# PCB3.net
KiCad netlist of a schematic drawn in EAGLE
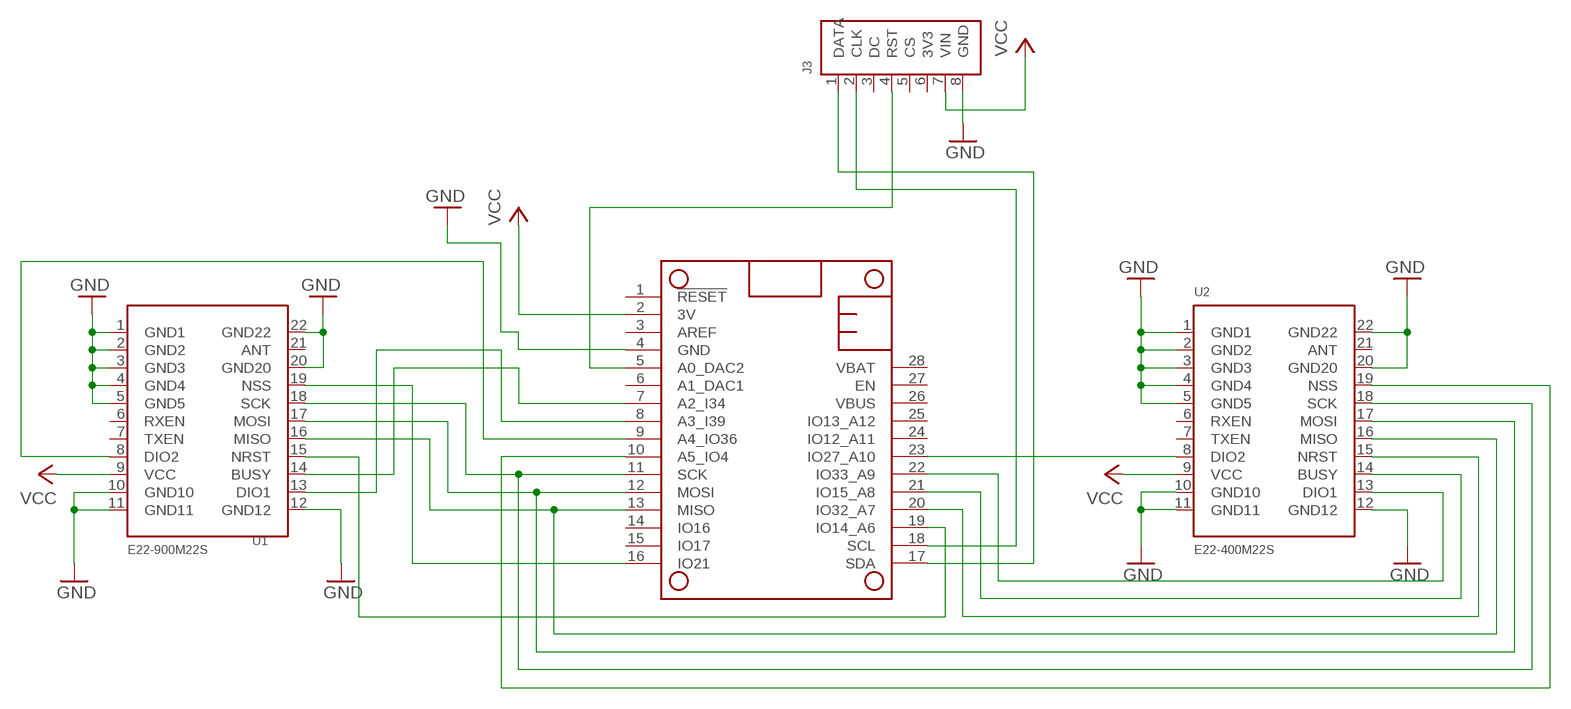
[diagram p0: schematic, sheet 1]

(export (version "E")
  (design (tool "Eeschema 10.0.6"))
  (components
    (comp (ref "J3")
      (value "1.3\"_128X64")
      (footprint "eagle-import:1.3__128X64_OLED")
      (libsource (lib "eagle-import") (part "1.3{dblquote}_128X64"))
    )
    (comp (ref "MS1")
      (value "FEATHERWING")
      (footprint "eagle-import:FEATHERWING")
      (libsource (lib "eagle-import") (part "FEATHERWING"))
    )
    (comp (ref "U1")
      (value "E22-900M22S")
      (footprint "eagle-import:E22")
      (libsource (lib "eagle-import") (part "E22-900M22S"))
    )
    (comp (ref "U2")
      (value "E22-400M22S")
      (footprint "eagle-import:E22")
      (libsource (lib "eagle-import") (part "E22-400M22S"))
    )
  )
  (nets
    (net (code "1") (name "/3V3") (class "Default")
      (node (ref "J3") (pin "6") (pinfunction "3V3_6") (pintype "power_in"))
    )
    (net (code "2") (name "/VBAT") (class "Default")
      (node (ref "MS1") (pin "28") (pinfunction "VBAT_28") (pintype "power_in"))
    )
    (net (code "3") (name "/VBUS") (class "Default")
      (node (ref "MS1") (pin "26") (pinfunction "VBUS_26") (pintype "power_in"))
    )
    (net (code "4") (name "GND") (class "Default")
      (node (ref "J3") (pin "8") (pinfunction "GND_8") (pintype "power_in"))
      (node (ref "MS1") (pin "4") (pinfunction "GND_4") (pintype "power_in"))
      (node (ref "U1") (pin "1") (pinfunction "GND1_1") (pintype "power_in"))
      (node (ref "U1") (pin "10") (pinfunction "GND10_10") (pintype "power_in"))
      (node (ref "U1") (pin "11") (pinfunction "GND11_11") (pintype "power_in"))
      (node (ref "U1") (pin "12") (pinfunction "GND12_12") (pintype "power_in"))
      (node (ref "U1") (pin "2") (pinfunction "GND2_2") (pintype "power_in"))
      (node (ref "U1") (pin "20") (pinfunction "GND20_20") (pintype "power_in"))
      (node (ref "U1") (pin "22") (pinfunction "GND22_22") (pintype "power_in"))
      (node (ref "U1") (pin "3") (pinfunction "GND3_3") (pintype "power_in"))
      (node (ref "U1") (pin "4") (pinfunction "GND4_4") (pintype "power_in"))
      (node (ref "U1") (pin "5") (pinfunction "GND5_5") (pintype "power_in"))
      (node (ref "U2") (pin "1") (pinfunction "GND1_1") (pintype "power_in"))
      (node (ref "U2") (pin "10") (pinfunction "GND10_10") (pintype "power_in"))
      (node (ref "U2") (pin "11") (pinfunction "GND11_11") (pintype "power_in"))
      (node (ref "U2") (pin "12") (pinfunction "GND12_12") (pintype "power_in"))
      (node (ref "U2") (pin "2") (pinfunction "GND2_2") (pintype "power_in"))
      (node (ref "U2") (pin "20") (pinfunction "GND20_20") (pintype "power_in"))
      (node (ref "U2") (pin "22") (pinfunction "GND22_22") (pintype "power_in"))
      (node (ref "U2") (pin "3") (pinfunction "GND3_3") (pintype "power_in"))
      (node (ref "U2") (pin "4") (pinfunction "GND4_4") (pintype "power_in"))
      (node (ref "U2") (pin "5") (pinfunction "GND5_5") (pintype "power_in"))
    )
    (net (code "5") (name "Net-(J3-CLK)") (class "Default")
      (node (ref "J3") (pin "2") (pinfunction "CLK_2") (pintype "bidirectional"))
      (node (ref "MS1") (pin "18") (pinfunction "SCL_18") (pintype "bidirectional"))
    )
    (net (code "6") (name "Net-(J3-DATA)") (class "Default")
      (node (ref "J3") (pin "1") (pinfunction "DATA_1") (pintype "bidirectional"))
      (node (ref "MS1") (pin "17") (pinfunction "SDA_17") (pintype "bidirectional"))
    )
    (net (code "7") (name "Net-(J3-RST)") (class "Default")
      (node (ref "J3") (pin "4") (pinfunction "RST_4") (pintype "bidirectional"))
      (node (ref "MS1") (pin "5") (pinfunction "A0_DAC2_5") (pintype "bidirectional"))
    )
    (net (code "8") (name "Net-(MS1-A2_I34)") (class "Default")
      (node (ref "MS1") (pin "7") (pinfunction "A2_I34_7") (pintype "bidirectional"))
      (node (ref "U1") (pin "14") (pinfunction "BUSY_14") (pintype "output"))
    )
    (net (code "9") (name "Net-(MS1-A3_I39)") (class "Default")
      (node (ref "MS1") (pin "8") (pinfunction "A3_I39_8") (pintype "bidirectional"))
      (node (ref "U1") (pin "13") (pinfunction "DIO1_13") (pintype "bidirectional"))
    )
    (net (code "10") (name "Net-(MS1-A4_IO36)") (class "Default")
      (node (ref "MS1") (pin "9") (pinfunction "A4_IO36_9") (pintype "bidirectional"))
      (node (ref "U1") (pin "8") (pinfunction "DIO2_8") (pintype "bidirectional"))
    )
    (net (code "11") (name "Net-(MS1-A5_IO4)") (class "Default")
      (node (ref "MS1") (pin "10") (pinfunction "A5_IO4_10") (pintype "bidirectional"))
      (node (ref "U2") (pin "19") (pinfunction "NSS_19") (pintype "input"))
    )
    (net (code "12") (name "Net-(MS1-IO14_A6)") (class "Default")
      (node (ref "MS1") (pin "19") (pinfunction "IO14_A6_19") (pintype "bidirectional"))
      (node (ref "U1") (pin "15") (pinfunction "NRST_15") (pintype "input"))
    )
    (net (code "13") (name "Net-(MS1-IO15_A8)") (class "Default")
      (node (ref "MS1") (pin "21") (pinfunction "IO15_A8_21") (pintype "bidirectional"))
      (node (ref "U2") (pin "14") (pinfunction "BUSY_14") (pintype "output"))
    )
    (net (code "14") (name "Net-(MS1-IO21)") (class "Default")
      (node (ref "MS1") (pin "16") (pinfunction "IO21_16") (pintype "bidirectional"))
      (node (ref "U1") (pin "19") (pinfunction "NSS_19") (pintype "input"))
    )
    (net (code "15") (name "Net-(MS1-IO27_A10)") (class "Default")
      (node (ref "MS1") (pin "23") (pinfunction "IO27_A10_23") (pintype "bidirectional"))
      (node (ref "U2") (pin "8") (pinfunction "DIO2_8") (pintype "bidirectional"))
    )
    (net (code "16") (name "Net-(MS1-IO32_A7)") (class "Default")
      (node (ref "MS1") (pin "20") (pinfunction "IO32_A7_20") (pintype "bidirectional"))
      (node (ref "U2") (pin "15") (pinfunction "NRST_15") (pintype "input"))
    )
    (net (code "17") (name "Net-(MS1-IO33_A9)") (class "Default")
      (node (ref "MS1") (pin "22") (pinfunction "IO33_A9_22") (pintype "bidirectional"))
      (node (ref "U2") (pin "13") (pinfunction "DIO1_13") (pintype "bidirectional"))
    )
    (net (code "18") (name "Net-(MS1-MISO)") (class "Default")
      (node (ref "MS1") (pin "13") (pinfunction "MISO_13") (pintype "bidirectional"))
      (node (ref "U1") (pin "16") (pinfunction "MISO_16") (pintype "output"))
      (node (ref "U2") (pin "16") (pinfunction "MISO_16") (pintype "output"))
    )
    (net (code "19") (name "Net-(MS1-MOSI)") (class "Default")
      (node (ref "MS1") (pin "12") (pinfunction "MOSI_12") (pintype "bidirectional"))
      (node (ref "U1") (pin "17") (pinfunction "MOSI_17") (pintype "input"))
      (node (ref "U2") (pin "17") (pinfunction "MOSI_17") (pintype "input"))
    )
    (net (code "20") (name "Net-(MS1-SCK)") (class "Default")
      (node (ref "MS1") (pin "11") (pinfunction "SCK_11") (pintype "bidirectional"))
      (node (ref "U1") (pin "18") (pinfunction "SCK_18") (pintype "input"))
      (node (ref "U2") (pin "18") (pinfunction "SCK_18") (pintype "input"))
    )
    (net (code "21") (name "VCC") (class "Default")
      (node (ref "J3") (pin "7") (pinfunction "VIN_7") (pintype "power_in"))
      (node (ref "MS1") (pin "2") (pinfunction "3V_2") (pintype "power_in"))
      (node (ref "U1") (pin "9") (pinfunction "VCC_9") (pintype "power_in"))
      (node (ref "U2") (pin "9") (pinfunction "VCC_9") (pintype "power_in"))
    )
    (net (code "22") (name "unconnected-(J3-CS-Pad5)") (class "Default")
      (node (ref "J3") (pin "5") (pinfunction "CS_5") (pintype "bidirectional"))
    )
    (net (code "23") (name "unconnected-(J3-DC-Pad3)") (class "Default")
      (node (ref "J3") (pin "3") (pinfunction "DC_3") (pintype "bidirectional"))
    )
    (net (code "24") (name "unconnected-(MS1-A1_DAC1-Pad6)") (class "Default")
      (node (ref "MS1") (pin "6") (pinfunction "A1_DAC1_6") (pintype "bidirectional"))
    )
    (net (code "25") (name "unconnected-(MS1-AREF-Pad3)") (class "Default")
      (node (ref "MS1") (pin "3") (pinfunction "AREF_3") (pintype "passive"))
    )
    (net (code "26") (name "unconnected-(MS1-EN-Pad27)") (class "Default")
      (node (ref "MS1") (pin "27") (pinfunction "EN_27") (pintype "passive"))
    )
    (net (code "27") (name "unconnected-(MS1-IO12_A11-Pad24)") (class "Default")
      (node (ref "MS1") (pin "24") (pinfunction "IO12_A11_24") (pintype "bidirectional"))
    )
    (net (code "28") (name "unconnected-(MS1-IO13_A12-Pad25)") (class "Default")
      (node (ref "MS1") (pin "25") (pinfunction "IO13_A12_25") (pintype "bidirectional"))
    )
    (net (code "29") (name "unconnected-(MS1-IO16-Pad14)") (class "Default")
      (node (ref "MS1") (pin "14") (pinfunction "IO16_14") (pintype "bidirectional"))
    )
    (net (code "30") (name "unconnected-(MS1-IO17-Pad15)") (class "Default")
      (node (ref "MS1") (pin "15") (pinfunction "IO17_15") (pintype "bidirectional"))
    )
    (net (code "31") (name "unconnected-(MS1-~{RESET}-Pad1)") (class "Default")
      (node (ref "MS1") (pin "1") (pinfunction "~{RESET}_1") (pintype "input"))
    )
    (net (code "32") (name "unconnected-(U1-ANT-Pad21)") (class "Default")
      (node (ref "U1") (pin "21") (pinfunction "ANT_21") (pintype "bidirectional"))
    )
    (net (code "33") (name "unconnected-(U1-RXEN-Pad6)") (class "Default")
      (node (ref "U1") (pin "6") (pinfunction "RXEN_6") (pintype "input"))
    )
    (net (code "34") (name "unconnected-(U1-TXEN-Pad7)") (class "Default")
      (node (ref "U1") (pin "7") (pinfunction "TXEN_7") (pintype "input"))
    )
    (net (code "35") (name "unconnected-(U2-ANT-Pad21)") (class "Default")
      (node (ref "U2") (pin "21") (pinfunction "ANT_21") (pintype "bidirectional"))
    )
    (net (code "36") (name "unconnected-(U2-RXEN-Pad6)") (class "Default")
      (node (ref "U2") (pin "6") (pinfunction "RXEN_6") (pintype "input"))
    )
    (net (code "37") (name "unconnected-(U2-TXEN-Pad7)") (class "Default")
      (node (ref "U2") (pin "7") (pinfunction "TXEN_7") (pintype "input"))
    )
  )
)
